# CXQuadcopter.net
KiCad netlist of a schematic drawn in Altium Designer
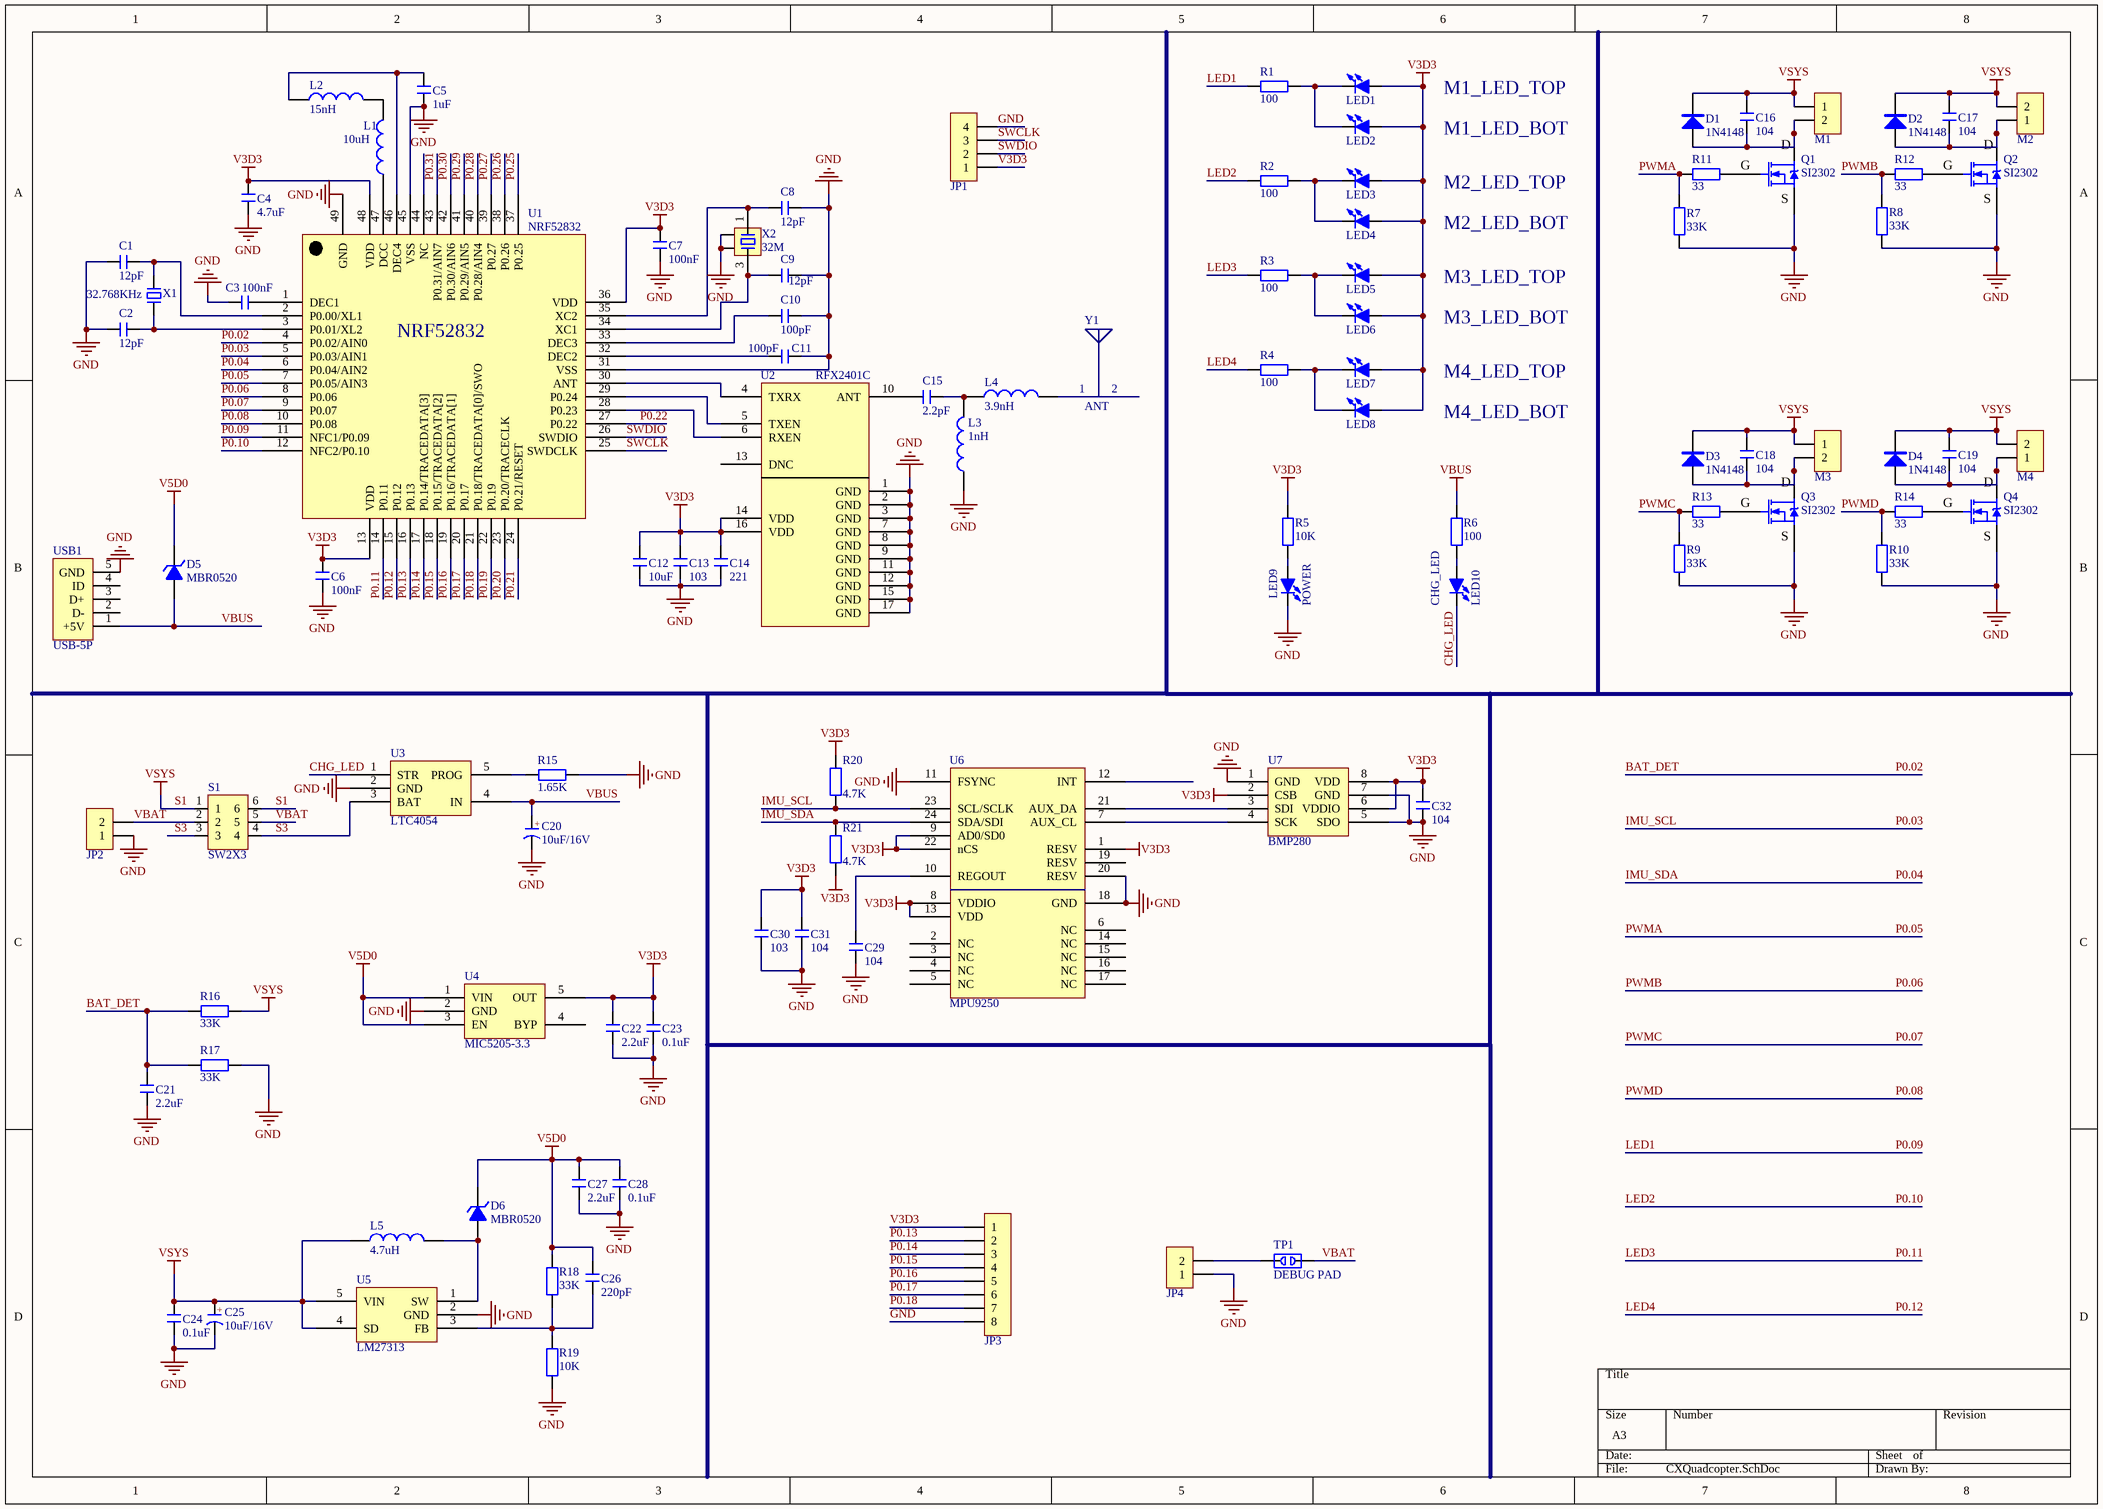
[diagram p0: CXQuadcopter.SchDoc]

(export (version "E")
  (design (tool "Eeschema 10.0.6"))
  (components
    (comp (ref "C1")
      (value "12pF")
      (footprint "C 0402")
      (description "无极性贴片电容")
      (fields (field (name "版权归属") "黎明电子style"))
      (libsource (lib "电阻-电容-电感") (part "C"))
    )
    (comp (ref "C2")
      (value "12pF")
      (footprint "C 0402")
      (description "无极性贴片电容")
      (fields (field (name "版权归属") "黎明电子style"))
      (libsource (lib "电阻-电容-电感") (part "C"))
    )
    (comp (ref "C3")
      (value "100nF")
      (footprint "C 0402")
      (description "无极性贴片电容")
      (fields (field (name "版权归属") "黎明电子style"))
      (libsource (lib "电阻-电容-电感") (part "C"))
    )
    (comp (ref "C4")
      (value "4.7uF")
      (footprint "C 0402")
      (description "无极性贴片电容")
      (fields (field (name "版权归属") "黎明电子style"))
      (libsource (lib "电阻-电容-电感") (part "C"))
    )
    (comp (ref "C5")
      (value "1uF")
      (footprint "C 0402")
      (description "无极性贴片电容")
      (fields (field (name "版权归属") "黎明电子style"))
      (libsource (lib "电阻-电容-电感") (part "C"))
    )
    (comp (ref "C6")
      (value "100nF")
      (footprint "C 0402")
      (description "无极性贴片电容")
      (fields (field (name "版权归属") "黎明电子style"))
      (libsource (lib "电阻-电容-电感") (part "C"))
    )
    (comp (ref "C7")
      (value "100nF")
      (footprint "C 0402")
      (description "无极性贴片电容")
      (fields (field (name "版权归属") "黎明电子style"))
      (libsource (lib "电阻-电容-电感") (part "C"))
    )
    (comp (ref "C8")
      (value "12pF")
      (footprint "C 0402")
      (description "无极性贴片电容")
      (fields (field (name "版权归属") "黎明电子style"))
      (libsource (lib "电阻-电容-电感") (part "C"))
    )
    (comp (ref "C9")
      (value "12pF")
      (footprint "C 0402")
      (description "无极性贴片电容")
      (fields (field (name "版权归属") "黎明电子style"))
      (libsource (lib "电阻-电容-电感") (part "C"))
    )
    (comp (ref "C10")
      (value "100pF")
      (footprint "C 0402")
      (description "无极性贴片电容")
      (fields (field (name "版权归属") "黎明电子style"))
      (libsource (lib "电阻-电容-电感") (part "C"))
    )
    (comp (ref "C11")
      (value "100pF")
      (footprint "C 0402")
      (description "无极性贴片电容")
      (fields (field (name "版权归属") "黎明电子style"))
      (libsource (lib "电阻-电容-电感") (part "C"))
    )
    (comp (ref "C12")
      (value "10uF")
      (footprint "C 0402")
      (description "无极性贴片电容")
      (fields (field (name "版权归属") "黎明电子style"))
      (libsource (lib "电阻-电容-电感") (part "C"))
    )
    (comp (ref "C13")
      (value "103")
      (footprint "C 0402")
      (description "无极性贴片电容")
      (fields (field (name "版权归属") "黎明电子style"))
      (libsource (lib "电阻-电容-电感") (part "C"))
    )
    (comp (ref "C14")
      (value "221")
      (footprint "C 0402")
      (description "无极性贴片电容")
      (fields (field (name "版权归属") "黎明电子style"))
      (libsource (lib "电阻-电容-电感") (part "C"))
    )
    (comp (ref "C15")
      (value "2.2pF")
      (footprint "C 0402")
      (description "无极性贴片电容")
      (fields (field (name "版权归属") "黎明电子style"))
      (libsource (lib "电阻-电容-电感") (part "C"))
    )
    (comp (ref "C16")
      (value "104")
      (footprint "C 0402")
      (description "无极性贴片电容")
      (fields (field (name "版权归属") "黎明电子style"))
      (libsource (lib "电阻-电容-电感") (part "C"))
    )
    (comp (ref "C17")
      (value "104")
      (footprint "C 0402")
      (description "无极性贴片电容")
      (fields (field (name "版权归属") "黎明电子style"))
      (libsource (lib "电阻-电容-电感") (part "C"))
    )
    (comp (ref "C18")
      (value "104")
      (footprint "C 0402")
      (description "无极性贴片电容")
      (fields (field (name "版权归属") "黎明电子style"))
      (libsource (lib "电阻-电容-电感") (part "C"))
    )
    (comp (ref "C19")
      (value "104")
      (footprint "C 0402")
      (description "无极性贴片电容")
      (fields (field (name "版权归属") "黎明电子style"))
      (libsource (lib "电阻-电容-电感") (part "C"))
    )
    (comp (ref "C20")
      (value "10uF/16V")
      (footprint "CD A(3216)")
      (description "贴片钽电容")
      (fields (field (name "版权归属") "黎明电子style"))
      (libsource (lib "电阻-电容-电感") (part "C-CD"))
    )
    (comp (ref "C21")
      (value "2.2uF")
      (footprint "C 0603")
      (description "无极性贴片电容")
      (fields (field (name "版权归属") "黎明电子style"))
      (libsource (lib "电阻-电容-电感") (part "C"))
    )
    (comp (ref "C22")
      (value "2.2uF")
      (footprint "C 0603")
      (description "无极性贴片电容")
      (fields (field (name "版权归属") "黎明电子style"))
      (libsource (lib "电阻-电容-电感") (part "C"))
    )
    (comp (ref "C23")
      (value "0.1uF")
      (footprint "C 0603")
      (description "无极性贴片电容")
      (fields (field (name "版权归属") "黎明电子style"))
      (libsource (lib "电阻-电容-电感") (part "C"))
    )
    (comp (ref "C24")
      (value "0.1uF")
      (footprint "C 0603")
      (description "无极性贴片电容")
      (fields (field (name "版权归属") "黎明电子style"))
      (libsource (lib "电阻-电容-电感") (part "C"))
    )
    (comp (ref "C25")
      (value "10uF/16V")
      (footprint "CD A(3216)")
      (description "贴片钽电容")
      (fields (field (name "版权归属") "黎明电子style"))
      (libsource (lib "电阻-电容-电感") (part "C-CD"))
    )
    (comp (ref "C26")
      (value "220pF")
      (footprint "C 0603")
      (description "无极性贴片电容")
      (fields (field (name "版权归属") "黎明电子style"))
      (libsource (lib "电阻-电容-电感") (part "C"))
    )
    (comp (ref "C27")
      (value "2.2uF")
      (footprint "C 0603")
      (description "无极性贴片电容")
      (fields (field (name "版权归属") "黎明电子style"))
      (libsource (lib "电阻-电容-电感") (part "C"))
    )
    (comp (ref "C28")
      (value "0.1uF")
      (footprint "C 0603")
      (description "无极性贴片电容")
      (fields (field (name "版权归属") "黎明电子style"))
      (libsource (lib "电阻-电容-电感") (part "C"))
    )
    (comp (ref "C29")
      (value "104")
      (footprint "C 0603")
      (description "无极性贴片电容")
      (fields (field (name "版权归属") "黎明电子style"))
      (libsource (lib "电阻-电容-电感") (part "C"))
    )
    (comp (ref "C30")
      (value "103")
      (footprint "C 0603")
      (description "无极性贴片电容")
      (fields (field (name "版权归属") "黎明电子style"))
      (libsource (lib "电阻-电容-电感") (part "C"))
    )
    (comp (ref "C31")
      (value "104")
      (footprint "C 0603")
      (description "无极性贴片电容")
      (fields (field (name "版权归属") "黎明电子style"))
      (libsource (lib "电阻-电容-电感") (part "C"))
    )
    (comp (ref "C32")
      (value "104")
      (footprint "C 0603")
      (description "无极性贴片电容")
      (fields (field (name "版权归属") "黎明电子style"))
      (libsource (lib "电阻-电容-电感") (part "C"))
    )
    (comp (ref "D1")
      (value "1N4148")
      (footprint "MINI_MELF (LL34)")
      (description "高速开关二极管")
      (fields (field (name "版权归属") "黎明电子style"))
      (libsource (lib "二极管-整流桥") (part "1N4148"))
    )
    (comp (ref "D2")
      (value "1N4148")
      (footprint "MINI_MELF (LL34)")
      (description "高速开关二极管")
      (fields (field (name "版权归属") "黎明电子style"))
      (libsource (lib "二极管-整流桥") (part "1N4148"))
    )
    (comp (ref "D3")
      (value "1N4148")
      (footprint "MINI_MELF (LL34)")
      (description "高速开关二极管")
      (fields (field (name "版权归属") "黎明电子style"))
      (libsource (lib "二极管-整流桥") (part "1N4148"))
    )
    (comp (ref "D4")
      (value "1N4148")
      (footprint "MINI_MELF (LL34)")
      (description "高速开关二极管")
      (fields (field (name "版权归属") "黎明电子style"))
      (libsource (lib "二极管-整流桥") (part "1N4148"))
    )
    (comp (ref "D5")
      (value "MBR0520")
      (footprint "DO-35")
      (description "12V/0.5W稳压管")
      (fields (field (name "版权归属") "黎明电子style"))
      (libsource (lib "二极管-整流桥") (part "1N4106"))
    )
    (comp (ref "D6")
      (value "MBR0520")
      (footprint "DO-35")
      (description "12V/0.5W稳压管")
      (fields (field (name "版权归属") "黎明电子style"))
      (libsource (lib "二极管-整流桥") (part "1N4106"))
    )
    (comp (ref "JP1")
      (value "HDR-1X4")
      (footprint "HDR2.54 S-W-4P")
      (description "4P接插件")
      (fields (field (name "版权归属") "黎明电子style"))
      (libsource (lib "接插件") (part "Header 4"))
    )
    (comp (ref "JP2")
      (value "HDR-1X2")
      (footprint "HDR-1X2")
      (description "2P接插件")
      (fields (field (name "版权归属") "黎明电子style"))
      (libsource (lib "") (part "Header 2_2"))
    )
    (comp (ref "JP3")
      (value "HDR-1X8")
      (footprint "HDR2.54 S-W-8P_M")
      (description "8P接插件")
      (fields (field (name "版权归属") "黎明电子style"))
      (libsource (lib "接插件") (part "Header 8"))
    )
    (comp (ref "JP4")
      (value "HDR-1X2")
      (footprint "HDR-1X2")
      (description "2P接插件")
      (fields (field (name "版权归属") "黎明电子style"))
      (libsource (lib "") (part "Header 2_2"))
    )
    (comp (ref "L1")
      (value "10uH")
      (footprint "L 0402")
      (description "小功率贴片电感")
      (fields (field (name "版权归属") "黎明电子style"))
      (libsource (lib "电阻-电容-电感") (part "L"))
    )
    (comp (ref "L2")
      (value "15nH")
      (footprint "L 0402")
      (description "小功率贴片电感")
      (fields (field (name "版权归属") "黎明电子style"))
      (libsource (lib "电阻-电容-电感") (part "L"))
    )
    (comp (ref "L3")
      (value "1nH")
      (footprint "L 0402")
      (description "小功率贴片电感")
      (fields (field (name "版权归属") "黎明电子style"))
      (libsource (lib "电阻-电容-电感") (part "L"))
    )
    (comp (ref "L4")
      (value "3.9nH")
      (footprint "L 0402")
      (description "小功率贴片电感")
      (fields (field (name "版权归属") "黎明电子style"))
      (libsource (lib "电阻-电容-电感") (part "L"))
    )
    (comp (ref "L5")
      (value "4.7uH")
      (footprint "L 0402")
      (description "小功率贴片电感")
      (fields (field (name "版权归属") "黎明电子style"))
      (libsource (lib "电阻-电容-电感") (part "L"))
    )
    (comp (ref "LED1")
      (value "红色")
      (footprint "LED 0603R")
      (description "贴片LED")
      (fields (field (name "版权归属") "黎明电子style"))
      (libsource (lib "LED") (part "LED-SMD"))
    )
    (comp (ref "LED2")
      (value "红色")
      (footprint "LED 0603R")
      (description "贴片LED")
      (fields (field (name "版权归属") "黎明电子style"))
      (libsource (lib "LED") (part "LED-SMD"))
    )
    (comp (ref "LED3")
      (value "红色")
      (footprint "LED 0603R")
      (description "贴片LED")
      (fields (field (name "版权归属") "黎明电子style"))
      (libsource (lib "LED") (part "LED-SMD"))
    )
    (comp (ref "LED4")
      (value "红色")
      (footprint "LED 0603R")
      (description "贴片LED")
      (fields (field (name "版权归属") "黎明电子style"))
      (libsource (lib "LED") (part "LED-SMD"))
    )
    (comp (ref "LED5")
      (value "红色")
      (footprint "LED 0603R")
      (description "贴片LED")
      (fields (field (name "版权归属") "黎明电子style"))
      (libsource (lib "LED") (part "LED-SMD"))
    )
    (comp (ref "LED6")
      (value "红色")
      (footprint "LED 0603R")
      (description "贴片LED")
      (fields (field (name "版权归属") "黎明电子style"))
      (libsource (lib "LED") (part "LED-SMD"))
    )
    (comp (ref "LED7")
      (value "红色")
      (footprint "LED 0603R")
      (description "贴片LED")
      (fields (field (name "版权归属") "黎明电子style"))
      (libsource (lib "LED") (part "LED-SMD"))
    )
    (comp (ref "LED8")
      (value "红色")
      (footprint "LED 0603R")
      (description "贴片LED")
      (fields (field (name "版权归属") "黎明电子style"))
      (libsource (lib "LED") (part "LED-SMD"))
    )
    (comp (ref "LED9")
      (value "POWER")
      (footprint "LED 0603R")
      (description "贴片LED")
      (fields (field (name "版权归属") "黎明电子style"))
      (libsource (lib "LED") (part "LED-SMD"))
    )
    (comp (ref "LED10")
      (value "CHG_LED")
      (footprint "LED 0603R")
      (description "贴片LED")
      (fields (field (name "版权归属") "黎明电子style"))
      (libsource (lib "LED") (part "LED-SMD"))
    )
    (comp (ref "M1")
      (value "HDR-1X2")
      (footprint "HDR-1X2")
      (description "2P接插件")
      (fields (field (name "版权归属") "黎明电子style"))
      (libsource (lib "接插件") (part "Header 2"))
    )
    (comp (ref "M2")
      (value "HDR-1X2")
      (footprint "HDR-1X2")
      (description "2P接插件")
      (fields (field (name "版权归属") "黎明电子style"))
      (libsource (lib "") (part "Header 2_1"))
    )
    (comp (ref "M3")
      (value "HDR-1X2")
      (footprint "HDR-1X2")
      (description "2P接插件")
      (fields (field (name "版权归属") "黎明电子style"))
      (libsource (lib "接插件") (part "Header 2"))
    )
    (comp (ref "M4")
      (value "HDR-1X2")
      (footprint "HDR-1X2")
      (description "2P接插件")
      (fields (field (name "版权归属") "黎明电子style"))
      (libsource (lib "") (part "Header 2_1"))
    )
    (comp (ref "Q1")
      (value "SI2302")
      (footprint "SOT23-3N")
      (description "N沟道场效应管")
      (fields (field (name "版权归属") "黎明电子style"))
      (libsource (lib "场效应管-可控硅") (part "SI2302"))
    )
    (comp (ref "Q2")
      (value "SI2302")
      (footprint "SOT23-3N")
      (description "N沟道场效应管")
      (fields (field (name "版权归属") "黎明电子style"))
      (libsource (lib "场效应管-可控硅") (part "SI2302"))
    )
    (comp (ref "Q3")
      (value "SI2302")
      (footprint "SOT23-3N")
      (description "N沟道场效应管")
      (fields (field (name "版权归属") "黎明电子style"))
      (libsource (lib "场效应管-可控硅") (part "SI2302"))
    )
    (comp (ref "Q4")
      (value "SI2302")
      (footprint "SOT23-3N")
      (description "N沟道场效应管")
      (fields (field (name "版权归属") "黎明电子style"))
      (libsource (lib "场效应管-可控硅") (part "SI2302"))
    )
    (comp (ref "R1")
      (value "100")
      (footprint "R 0603")
      (description "贴片电阻")
      (fields (field (name "版权归属") "黎明电子style"))
      (libsource (lib "电阻-电容-电感") (part "R"))
    )
    (comp (ref "R2")
      (value "100")
      (footprint "R 0603")
      (description "贴片电阻")
      (fields (field (name "版权归属") "黎明电子style"))
      (libsource (lib "电阻-电容-电感") (part "R"))
    )
    (comp (ref "R3")
      (value "100")
      (footprint "R 0603")
      (description "贴片电阻")
      (fields (field (name "版权归属") "黎明电子style"))
      (libsource (lib "电阻-电容-电感") (part "R"))
    )
    (comp (ref "R4")
      (value "100")
      (footprint "R 0603")
      (description "贴片电阻")
      (fields (field (name "版权归属") "黎明电子style"))
      (libsource (lib "电阻-电容-电感") (part "R"))
    )
    (comp (ref "R5")
      (value "10K")
      (footprint "R 0603")
      (description "贴片电阻")
      (fields (field (name "版权归属") "黎明电子style"))
      (libsource (lib "电阻-电容-电感") (part "R"))
    )
    (comp (ref "R6")
      (value "100")
      (footprint "R 0603")
      (description "贴片电阻")
      (fields (field (name "版权归属") "黎明电子style"))
      (libsource (lib "电阻-电容-电感") (part "R"))
    )
    (comp (ref "R7")
      (value "33K")
      (footprint "R 0603")
      (description "贴片电阻")
      (fields (field (name "版权归属") "黎明电子style"))
      (libsource (lib "电阻-电容-电感") (part "R"))
    )
    (comp (ref "R8")
      (value "33K")
      (footprint "R 0603")
      (description "贴片电阻")
      (fields (field (name "版权归属") "黎明电子style"))
      (libsource (lib "电阻-电容-电感") (part "R"))
    )
    (comp (ref "R9")
      (value "33K")
      (footprint "R 0603")
      (description "贴片电阻")
      (fields (field (name "版权归属") "黎明电子style"))
      (libsource (lib "电阻-电容-电感") (part "R"))
    )
    (comp (ref "R10")
      (value "33K")
      (footprint "R 0603")
      (description "贴片电阻")
      (fields (field (name "版权归属") "黎明电子style"))
      (libsource (lib "电阻-电容-电感") (part "R"))
    )
    (comp (ref "R11")
      (value "33")
      (footprint "R 0603")
      (description "贴片电阻")
      (fields (field (name "版权归属") "黎明电子style"))
      (libsource (lib "电阻-电容-电感") (part "R"))
    )
    (comp (ref "R12")
      (value "33")
      (footprint "R 0603")
      (description "贴片电阻")
      (fields (field (name "版权归属") "黎明电子style"))
      (libsource (lib "电阻-电容-电感") (part "R"))
    )
    (comp (ref "R13")
      (value "33")
      (footprint "R 0603")
      (description "贴片电阻")
      (fields (field (name "版权归属") "黎明电子style"))
      (libsource (lib "电阻-电容-电感") (part "R"))
    )
    (comp (ref "R14")
      (value "33")
      (footprint "R 0603")
      (description "贴片电阻")
      (fields (field (name "版权归属") "黎明电子style"))
      (libsource (lib "电阻-电容-电感") (part "R"))
    )
    (comp (ref "R15")
      (value "1.65K")
      (footprint "R 0603")
      (description "贴片电阻")
      (fields (field (name "版权归属") "黎明电子style"))
      (libsource (lib "电阻-电容-电感") (part "R"))
    )
    (comp (ref "R16")
      (value "33K")
      (footprint "R 0603")
      (description "贴片电阻")
      (fields (field (name "版权归属") "黎明电子style"))
      (libsource (lib "电阻-电容-电感") (part "R"))
    )
    (comp (ref "R17")
      (value "33K")
      (footprint "R 0603")
      (description "贴片电阻")
      (fields (field (name "版权归属") "黎明电子style"))
      (libsource (lib "电阻-电容-电感") (part "R"))
    )
    (comp (ref "R18")
      (value "33K")
      (footprint "R 0603")
      (description "贴片电阻")
      (fields (field (name "版权归属") "黎明电子style"))
      (libsource (lib "电阻-电容-电感") (part "R"))
    )
    (comp (ref "R19")
      (value "10K")
      (footprint "R 0603")
      (description "贴片电阻")
      (fields (field (name "版权归属") "黎明电子style"))
      (libsource (lib "电阻-电容-电感") (part "R"))
    )
    (comp (ref "R20")
      (value "4.7K")
      (footprint "R 0603")
      (description "贴片电阻")
      (fields (field (name "版权归属") "黎明电子style"))
      (libsource (lib "电阻-电容-电感") (part "R"))
    )
    (comp (ref "R21")
      (value "4.7K")
      (footprint "R 0603")
      (description "贴片电阻")
      (fields (field (name "版权归属") "黎明电子style"))
      (libsource (lib "电阻-电容-电感") (part "R"))
    )
    (comp (ref "S1") (value "SW2X3") (libsource (lib "ZhuhcADLib") (part "Switch")))
    (comp (ref "TP1")
      (value "DEBUG PAD")
      (footprint "DEBUG PAD2")
      (description "调试断点焊盘")
      (fields (field (name "版权归属") "黎明电子style"))
      (libsource (lib "未分类器件") (part "DEBUG"))
    )
    (comp (ref "U1") (value "NRF52832") (libsource (lib "ZhuhcADLib") (part "NRF52832")))
    (comp (ref "U2") (value "RFX2401C") (libsource (lib "ZhuhcADLib") (part "RFX2401C")))
    (comp (ref "U3") (value "LTC4054") (libsource (lib "ZhuhcADLib") (part "LTC4054")))
    (comp (ref "U4") (value "MIC5205-3.3") (libsource (lib "ZhuhcADLib") (part "MIC5205-3.3")))
    (comp (ref "U5") (value "LM27313") (libsource (lib "ZhuhcADLib") (part "LM27313")))
    (comp (ref "U6") (value "MPU9250") (libsource (lib "ZhuhcADLib") (part "MPU9250")))
    (comp (ref "U7") (value "BMP280") (libsource (lib "ZhuhcADLib") (part "BMP280")))
    (comp (ref "USB1")
      (value "USB-5P")
      (footprint "USB-MICRO_A")
      (description "微型USB母座")
      (fields (field (name "版权归属") "黎明电子style"))
      (libsource (lib "接口类") (part "USB-5P"))
    )
    (comp (ref "X1")
      (value "32.768KHz")
      (footprint "XTAL-3X8H")
      (description "2脚晶振")
      (fields (field (name "版权归属") "黎明电子style"))
      (libsource (lib "保险丝-晶振") (part "XTAL-2"))
    )
    (comp (ref "X2")
      (value "32M")
      (footprint "XTAL-5032")
      (description "4脚晶振")
      (fields (field (name "版权归属") "黎明电子style"))
      (libsource (lib "保险丝-晶振") (part "XTAL-4"))
    )
    (comp (ref "Y1") (value "ANT") (libsource (lib "ZhuhcADLib") (part "ANT")))
  )
  (nets
    (net (code "1") (name "/BAT_DET") (class "Default")
      (node (ref "C21") (pin "2") (pinfunction "2_2") (pintype "passive"))
      (node (ref "R16") (pin "1") (pinfunction "1_1") (pintype "passive"))
      (node (ref "R17") (pin "1") (pinfunction "1_1") (pintype "passive"))
      (node (ref "U1") (pin "4") (pinfunction "P0.02/AIN0_4") (pintype "passive"))
    )
    (net (code "2") (name "/CHG_LED") (class "Default")
      (node (ref "LED10") (pin "2") (pinfunction "K_2") (pintype "passive"))
      (node (ref "U3") (pin "1") (pinfunction "STR_1") (pintype "passive"))
    )
    (net (code "3") (name "/IMU_SCL") (class "Default")
      (node (ref "R20") (pin "1") (pinfunction "1_1") (pintype "passive"))
      (node (ref "U1") (pin "5") (pinfunction "P0.03/AIN1_5") (pintype "passive"))
      (node (ref "U6") (pin "23") (pinfunction "SCL/SCLK_23") (pintype "passive"))
    )
    (net (code "4") (name "/IMU_SDA") (class "Default")
      (node (ref "R21") (pin "2") (pinfunction "2_2") (pintype "passive"))
      (node (ref "U1") (pin "6") (pinfunction "P0.04/AIN2_6") (pintype "passive"))
      (node (ref "U6") (pin "24") (pinfunction "SDA/SDI_24") (pintype "passive"))
    )
    (net (code "5") (name "/LED1") (class "Default")
      (node (ref "R1") (pin "2") (pinfunction "2_2") (pintype "passive"))
      (node (ref "U1") (pin "11") (pinfunction "NFC1/P0.09_11") (pintype "passive"))
    )
    (net (code "6") (name "/LED2") (class "Default")
      (node (ref "R2") (pin "2") (pinfunction "2_2") (pintype "passive"))
      (node (ref "U1") (pin "12") (pinfunction "NFC2/P0.10_12") (pintype "passive"))
    )
    (net (code "7") (name "/LED3") (class "Default")
      (node (ref "R3") (pin "2") (pinfunction "2_2") (pintype "passive"))
      (node (ref "U1") (pin "14") (pinfunction "P0.11_14") (pintype "passive"))
    )
    (net (code "8") (name "/LED4") (class "Default")
      (node (ref "R4") (pin "2") (pinfunction "2_2") (pintype "passive"))
      (node (ref "U1") (pin "15") (pinfunction "P0.12_15") (pintype "passive"))
    )
    (net (code "9") (name "/P0.05") (class "Default")
      (node (ref "R11") (pin "2") (pinfunction "2_2") (pintype "passive"))
      (node (ref "R7") (pin "2") (pinfunction "2_2") (pintype "passive"))
      (node (ref "U1") (pin "7") (pinfunction "P0.05/AIN3_7") (pintype "passive"))
    )
    (net (code "10") (name "/P0.06") (class "Default")
      (node (ref "R12") (pin "2") (pinfunction "2_2") (pintype "passive"))
      (node (ref "R8") (pin "2") (pinfunction "2_2") (pintype "passive"))
      (node (ref "U1") (pin "8") (pinfunction "P0.06_8") (pintype "passive"))
    )
    (net (code "11") (name "/P0.07") (class "Default")
      (node (ref "R13") (pin "2") (pinfunction "2_2") (pintype "passive"))
      (node (ref "R9") (pin "2") (pinfunction "2_2") (pintype "passive"))
      (node (ref "U1") (pin "9") (pinfunction "P0.07_9") (pintype "passive"))
    )
    (net (code "12") (name "/P0.08") (class "Default")
      (node (ref "R10") (pin "2") (pinfunction "2_2") (pintype "passive"))
      (node (ref "R14") (pin "2") (pinfunction "2_2") (pintype "passive"))
      (node (ref "U1") (pin "10") (pinfunction "P0.08_10") (pintype "passive"))
    )
    (net (code "13") (name "/P0.13") (class "Default")
      (node (ref "JP3") (pin "2") (pinfunction "2_2") (pintype "passive"))
      (node (ref "U1") (pin "16") (pinfunction "P0.13_16") (pintype "passive"))
    )
    (net (code "14") (name "/P0.14") (class "Default")
      (node (ref "JP3") (pin "3") (pinfunction "3_3") (pintype "passive"))
      (node (ref "U1") (pin "17") (pinfunction "P0.14/TRACEDATA[3]_17") (pintype "passive"))
    )
    (net (code "15") (name "/P0.15") (class "Default")
      (node (ref "JP3") (pin "4") (pinfunction "4_4") (pintype "passive"))
      (node (ref "U1") (pin "18") (pinfunction "P0.15/TRACEDATA[2]_18") (pintype "passive"))
    )
    (net (code "16") (name "/P0.16") (class "Default")
      (node (ref "JP3") (pin "5") (pinfunction "5_5") (pintype "passive"))
      (node (ref "U1") (pin "19") (pinfunction "P0.16/TRACEDATA[1]_19") (pintype "passive"))
    )
    (net (code "17") (name "/P0.17") (class "Default")
      (node (ref "JP3") (pin "6") (pinfunction "6_6") (pintype "passive"))
      (node (ref "U1") (pin "20") (pinfunction "P0.17_20") (pintype "passive"))
    )
    (net (code "18") (name "/P0.18") (class "Default")
      (node (ref "JP3") (pin "7") (pinfunction "7_7") (pintype "passive"))
      (node (ref "U1") (pin "21") (pinfunction "P0.18/TRACEDATA[0]/SWO_21") (pintype "passive"))
    )
    (net (code "19") (name "/P0.19") (class "Default")
      (node (ref "U1") (pin "22") (pinfunction "P0.19_22") (pintype "passive"))
    )
    (net (code "20") (name "/P0.20") (class "Default")
      (node (ref "U1") (pin "23") (pinfunction "P0.20/TRACECLK_23") (pintype "passive"))
    )
    (net (code "21") (name "/P0.21") (class "Default")
      (node (ref "U1") (pin "24") (pinfunction "P0.21/RESET_24") (pintype "passive"))
    )
    (net (code "22") (name "/P0.22") (class "Default")
      (node (ref "U1") (pin "27") (pinfunction "P0.22_27") (pintype "passive"))
    )
    (net (code "23") (name "/P0.25") (class "Default")
      (node (ref "U1") (pin "37") (pinfunction "P0.25_37") (pintype "passive"))
    )
    (net (code "24") (name "/P0.26") (class "Default")
      (node (ref "U1") (pin "38") (pinfunction "P0.26_38") (pintype "passive"))
    )
    (net (code "25") (name "/P0.27") (class "Default")
      (node (ref "U1") (pin "39") (pinfunction "P0.27_39") (pintype "passive"))
    )
    (net (code "26") (name "/P0.28") (class "Default")
      (node (ref "U1") (pin "40") (pinfunction "P0.28/AIN4_40") (pintype "passive"))
    )
    (net (code "27") (name "/P0.29") (class "Default")
      (node (ref "U1") (pin "41") (pinfunction "P0.29/AIN5_41") (pintype "passive"))
    )
    (net (code "28") (name "/P0.30") (class "Default")
      (node (ref "U1") (pin "42") (pinfunction "P0.30/AIN6_42") (pintype "passive"))
    )
    (net (code "29") (name "/P0.31") (class "Default")
      (node (ref "U1") (pin "43") (pinfunction "P0.31/AIN7_43") (pintype "passive"))
    )
    (net (code "30") (name "/S3") (class "Default")
      (node (ref "S1") (pin "3") (pinfunction "3_3") (pintype "passive"))
      (node (ref "S1") (pin "4") (pinfunction "4_4") (pintype "passive"))
      (node (ref "U3") (pin "3") (pinfunction "BAT_3") (pintype "passive"))
    )
    (net (code "31") (name "/SWCLK") (class "Default")
      (node (ref "JP1") (pin "3") (pinfunction "3_3") (pintype "passive"))
      (node (ref "U1") (pin "25") (pinfunction "SWDCLK_25") (pintype "passive"))
    )
    (net (code "32") (name "/SWDIO") (class "Default")
      (node (ref "JP1") (pin "2") (pinfunction "2_2") (pintype "passive"))
      (node (ref "U1") (pin "26") (pinfunction "SWDIO_26") (pintype "passive"))
    )
    (net (code "33") (name "/VBAT") (class "Default")
      (node (ref "JP2") (pin "2") (pinfunction "2_2") (pintype "passive"))
      (node (ref "S1") (pin "2") (pinfunction "2_2") (pintype "passive"))
      (node (ref "S1") (pin "5") (pinfunction "5_5") (pintype "passive"))
      (node (ref "TP1") (pin "2") (pinfunction "2_2") (pintype "passive"))
    )
    (net (code "34") (name "GND") (class "Default")
      (node (ref "C1") (pin "1") (pinfunction "1_1") (pintype "passive"))
      (node (ref "C10") (pin "2") (pinfunction "2_2") (pintype "passive"))
      (node (ref "C11") (pin "2") (pinfunction "2_2") (pintype "passive"))
      (node (ref "C12") (pin "1") (pinfunction "1_1") (pintype "passive"))
      (node (ref "C13") (pin "1") (pinfunction "1_1") (pintype "passive"))
      (node (ref "C14") (pin "1") (pinfunction "1_1") (pintype "passive"))
      (node (ref "C2") (pin "1") (pinfunction "1_1") (pintype "passive"))
      (node (ref "C20") (pin "2") (pinfunction "K_2") (pintype "passive"))
      (node (ref "C21") (pin "1") (pinfunction "1_1") (pintype "passive"))
      (node (ref "C22") (pin "1") (pinfunction "1_1") (pintype "passive"))
      (node (ref "C23") (pin "1") (pinfunction "1_1") (pintype "passive"))
      (node (ref "C24") (pin "1") (pinfunction "1_1") (pintype "passive"))
      (node (ref "C25") (pin "2") (pinfunction "K_2") (pintype "passive"))
      (node (ref "C27") (pin "1") (pinfunction "1_1") (pintype "passive"))
      (node (ref "C28") (pin "1") (pinfunction "1_1") (pintype "passive"))
      (node (ref "C29") (pin "1") (pinfunction "1_1") (pintype "passive"))
      (node (ref "C3") (pin "1") (pinfunction "1_1") (pintype "passive"))
      (node (ref "C30") (pin "1") (pinfunction "1_1") (pintype "passive"))
      (node (ref "C31") (pin "1") (pinfunction "1_1") (pintype "passive"))
      (node (ref "C32") (pin "1") (pinfunction "1_1") (pintype "passive"))
      (node (ref "C4") (pin "1") (pinfunction "1_1") (pintype "passive"))
      (node (ref "C5") (pin "1") (pinfunction "1_1") (pintype "passive"))
      (node (ref "C6") (pin "1") (pinfunction "1_1") (pintype "passive"))
      (node (ref "C7") (pin "1") (pinfunction "1_1") (pintype "passive"))
      (node (ref "C8") (pin "2") (pinfunction "2_2") (pintype "passive"))
      (node (ref "C9") (pin "2") (pinfunction "2_2") (pintype "passive"))
      (node (ref "JP1") (pin "4") (pinfunction "4_4") (pintype "passive"))
      (node (ref "JP2") (pin "1") (pinfunction "1_1") (pintype "passive"))
      (node (ref "JP3") (pin "8") (pinfunction "8_8") (pintype "passive"))
      (node (ref "JP4") (pin "1") (pinfunction "1_1") (pintype "passive"))
      (node (ref "L3") (pin "1") (pinfunction "1_1") (pintype "passive"))
      (node (ref "LED9") (pin "2") (pinfunction "K_2") (pintype "passive"))
      (node (ref "Q1") (pin "2") (pinfunction "S_2") (pintype "passive"))
      (node (ref "Q2") (pin "2") (pinfunction "S_2") (pintype "passive"))
      (node (ref "Q3") (pin "2") (pinfunction "S_2") (pintype "passive"))
      (node (ref "Q4") (pin "2") (pinfunction "S_2") (pintype "passive"))
      (node (ref "R10") (pin "1") (pinfunction "1_1") (pintype "passive"))
      (node (ref "R15") (pin "2") (pinfunction "2_2") (pintype "passive"))
      (node (ref "R17") (pin "2") (pinfunction "2_2") (pintype "passive"))
      (node (ref "R19") (pin "1") (pinfunction "1_1") (pintype "passive"))
      (node (ref "R7") (pin "1") (pinfunction "1_1") (pintype "passive"))
      (node (ref "R8") (pin "1") (pinfunction "1_1") (pintype "passive"))
      (node (ref "R9") (pin "1") (pinfunction "1_1") (pintype "passive"))
      (node (ref "U1") (pin "31") (pinfunction "VSS_31") (pintype "passive"))
      (node (ref "U1") (pin "45") (pinfunction "VSS_45") (pintype "passive"))
      (node (ref "U1") (pin "49") (pinfunction "GND_49") (pintype "passive"))
      (node (ref "U2") (pin "1") (pinfunction "GND_1") (pintype "passive"))
      (node (ref "U2") (pin "11") (pinfunction "GND_11") (pintype "passive"))
      (node (ref "U2") (pin "12") (pinfunction "GND_12") (pintype "passive"))
      (node (ref "U2") (pin "15") (pinfunction "GND_15") (pintype "passive"))
      (node (ref "U2") (pin "17") (pinfunction "GND_17") (pintype "passive"))
      (node (ref "U2") (pin "2") (pinfunction "GND_2") (pintype "passive"))
      (node (ref "U2") (pin "3") (pinfunction "GND_3") (pintype "passive"))
      (node (ref "U2") (pin "7") (pinfunction "GND_7") (pintype "passive"))
      (node (ref "U2") (pin "8") (pinfunction "GND_8") (pintype "passive"))
      (node (ref "U2") (pin "9") (pinfunction "GND_9") (pintype "passive"))
      (node (ref "U3") (pin "2") (pinfunction "GND_2") (pintype "passive"))
      (node (ref "U4") (pin "2") (pinfunction "GND_2") (pintype "passive"))
      (node (ref "U5") (pin "2") (pinfunction "GND_2") (pintype "passive"))
      (node (ref "U6") (pin "11") (pinfunction "FSYNC_11") (pintype "passive"))
      (node (ref "U6") (pin "18") (pinfunction "GND_18") (pintype "passive"))
      (node (ref "U6") (pin "20") (pinfunction "RESV_20") (pintype "passive"))
      (node (ref "U7") (pin "1") (pinfunction "GND_1") (pintype "passive"))
      (node (ref "U7") (pin "5") (pinfunction "SDO_5") (pintype "passive"))
      (node (ref "U7") (pin "7") (pinfunction "GND_7") (pintype "passive"))
      (node (ref "USB1") (pin "5") (pinfunction "GND_5") (pintype "passive"))
      (node (ref "X2") (pin "2") (pinfunction "2_2") (pintype "passive"))
      (node (ref "X2") (pin "4") (pinfunction "4_4") (pintype "passive"))
    )
    (net (code "35") (name "Net-(C15-Pad1)") (class "Default")
      (node (ref "C15") (pin "1") (pinfunction "1_1") (pintype "passive"))
      (node (ref "L3") (pin "2") (pinfunction "2_2") (pintype "passive"))
      (node (ref "L4") (pin "1") (pinfunction "1_1") (pintype "passive"))
    )
    (net (code "36") (name "Net-(D1-A)") (class "Default")
      (node (ref "C16") (pin "2") (pinfunction "2_2") (pintype "passive"))
      (node (ref "D1") (pin "1") (pinfunction "A_1") (pintype "passive"))
      (node (ref "M1") (pin "2") (pinfunction "2_2") (pintype "passive"))
      (node (ref "Q1") (pin "3") (pinfunction "D_3") (pintype "passive"))
    )
    (net (code "37") (name "Net-(D2-A)") (class "Default")
      (node (ref "C17") (pin "2") (pinfunction "2_2") (pintype "passive"))
      (node (ref "D2") (pin "1") (pinfunction "A_1") (pintype "passive"))
      (node (ref "M2") (pin "1") (pinfunction "1_1") (pintype "passive"))
      (node (ref "Q2") (pin "3") (pinfunction "D_3") (pintype "passive"))
    )
    (net (code "38") (name "Net-(D3-A)") (class "Default")
      (node (ref "C18") (pin "2") (pinfunction "2_2") (pintype "passive"))
      (node (ref "D3") (pin "1") (pinfunction "A_1") (pintype "passive"))
      (node (ref "M3") (pin "2") (pinfunction "2_2") (pintype "passive"))
      (node (ref "Q3") (pin "3") (pinfunction "D_3") (pintype "passive"))
    )
    (net (code "39") (name "Net-(D4-A)") (class "Default")
      (node (ref "C19") (pin "2") (pinfunction "2_2") (pintype "passive"))
      (node (ref "D4") (pin "1") (pinfunction "A_1") (pintype "passive"))
      (node (ref "M4") (pin "1") (pinfunction "1_1") (pintype "passive"))
      (node (ref "Q4") (pin "3") (pinfunction "D_3") (pintype "passive"))
    )
    (net (code "40") (name "Net-(D6-A)") (class "Default")
      (node (ref "D6") (pin "1") (pinfunction "A_1") (pintype "passive"))
      (node (ref "L5") (pin "2") (pinfunction "2_2") (pintype "passive"))
      (node (ref "U5") (pin "1") (pinfunction "SW_1") (pintype "passive"))
    )
    (net (code "41") (name "Net-(JP4-Pad2)") (class "Default")
      (node (ref "JP4") (pin "2") (pinfunction "2_2") (pintype "passive"))
      (node (ref "TP1") (pin "1") (pinfunction "1_1") (pintype "passive"))
    )
    (net (code "42") (name "Net-(L1-Pad2)") (class "Default")
      (node (ref "L1") (pin "2") (pinfunction "2_2") (pintype "passive"))
      (node (ref "L2") (pin "2") (pinfunction "2_2") (pintype "passive"))
    )
    (net (code "43") (name "Net-(L4-Pad2)") (class "Default")
      (node (ref "L4") (pin "2") (pinfunction "2_2") (pintype "passive"))
      (node (ref "Y1") (pin "1") (pinfunction "1_1") (pintype "passive"))
    )
    (net (code "44") (name "Net-(LED1-K)") (class "Default")
      (node (ref "LED1") (pin "2") (pinfunction "K_2") (pintype "passive"))
      (node (ref "LED2") (pin "2") (pinfunction "K_2") (pintype "passive"))
      (node (ref "R1") (pin "1") (pinfunction "1_1") (pintype "passive"))
    )
    (net (code "45") (name "Net-(LED3-K)") (class "Default")
      (node (ref "LED3") (pin "2") (pinfunction "K_2") (pintype "passive"))
      (node (ref "LED4") (pin "2") (pinfunction "K_2") (pintype "passive"))
      (node (ref "R2") (pin "1") (pinfunction "1_1") (pintype "passive"))
    )
    (net (code "46") (name "Net-(LED5-K)") (class "Default")
      (node (ref "LED5") (pin "2") (pinfunction "K_2") (pintype "passive"))
      (node (ref "LED6") (pin "2") (pinfunction "K_2") (pintype "passive"))
      (node (ref "R3") (pin "1") (pinfunction "1_1") (pintype "passive"))
    )
    (net (code "47") (name "Net-(LED7-K)") (class "Default")
      (node (ref "LED7") (pin "2") (pinfunction "K_2") (pintype "passive"))
      (node (ref "LED8") (pin "2") (pinfunction "K_2") (pintype "passive"))
      (node (ref "R4") (pin "1") (pinfunction "1_1") (pintype "passive"))
    )
    (net (code "48") (name "Net-(LED9-A)") (class "Default")
      (node (ref "LED9") (pin "1") (pinfunction "A_1") (pintype "passive"))
      (node (ref "R5") (pin "2") (pinfunction "2_2") (pintype "passive"))
    )
    (net (code "49") (name "Net-(LED10-A)") (class "Default")
      (node (ref "LED10") (pin "1") (pinfunction "A_1") (pintype "passive"))
      (node (ref "R6") (pin "2") (pinfunction "2_2") (pintype "passive"))
    )
    (net (code "50") (name "Net-(Q1-G)") (class "Default")
      (node (ref "Q1") (pin "1") (pinfunction "G_1") (pintype "passive"))
      (node (ref "R11") (pin "1") (pinfunction "1_1") (pintype "passive"))
    )
    (net (code "51") (name "Net-(Q2-G)") (class "Default")
      (node (ref "Q2") (pin "1") (pinfunction "G_1") (pintype "passive"))
      (node (ref "R12") (pin "1") (pinfunction "1_1") (pintype "passive"))
    )
    (net (code "52") (name "Net-(Q3-G)") (class "Default")
      (node (ref "Q3") (pin "1") (pinfunction "G_1") (pintype "passive"))
      (node (ref "R13") (pin "1") (pinfunction "1_1") (pintype "passive"))
    )
    (net (code "53") (name "Net-(Q4-G)") (class "Default")
      (node (ref "Q4") (pin "1") (pinfunction "G_1") (pintype "passive"))
      (node (ref "R14") (pin "1") (pinfunction "1_1") (pintype "passive"))
    )
    (net (code "54") (name "Net-(U1-ANT)") (class "Default")
      (node (ref "U1") (pin "30") (pinfunction "ANT_30") (pintype "passive"))
      (node (ref "U2") (pin "4") (pinfunction "TXRX_4") (pintype "passive"))
    )
    (net (code "55") (name "Net-(U1-DCC)") (class "Default")
      (node (ref "L1") (pin "1") (pinfunction "1_1") (pintype "passive"))
      (node (ref "U1") (pin "47") (pinfunction "DCC_47") (pintype "passive"))
    )
    (net (code "56") (name "Net-(U1-DEC1)") (class "Default")
      (node (ref "C3") (pin "2") (pinfunction "2_2") (pintype "passive"))
      (node (ref "U1") (pin "1") (pinfunction "DEC1_1") (pintype "passive"))
    )
    (net (code "57") (name "Net-(U1-DEC2)") (class "Default")
      (node (ref "C11") (pin "1") (pinfunction "1_1") (pintype "passive"))
      (node (ref "U1") (pin "32") (pinfunction "DEC2_32") (pintype "passive"))
    )
    (net (code "58") (name "Net-(U1-DEC3)") (class "Default")
      (node (ref "C10") (pin "1") (pinfunction "1_1") (pintype "passive"))
      (node (ref "U1") (pin "33") (pinfunction "DEC3_33") (pintype "passive"))
    )
    (net (code "59") (name "Net-(U1-DEC4)") (class "Default")
      (node (ref "C5") (pin "2") (pinfunction "2_2") (pintype "passive"))
      (node (ref "L2") (pin "1") (pinfunction "1_1") (pintype "passive"))
      (node (ref "U1") (pin "46") (pinfunction "DEC4_46") (pintype "passive"))
    )
    (net (code "60") (name "Net-(U1-P0.00{slash}XL1)") (class "Default")
      (node (ref "C1") (pin "2") (pinfunction "2_2") (pintype "passive"))
      (node (ref "U1") (pin "2") (pinfunction "P0.00/XL1_2") (pintype "passive"))
      (node (ref "X1") (pin "2") (pinfunction "2_2") (pintype "passive"))
    )
    (net (code "61") (name "Net-(U1-P0.01{slash}XL2)") (class "Default")
      (node (ref "C2") (pin "2") (pinfunction "2_2") (pintype "passive"))
      (node (ref "U1") (pin "3") (pinfunction "P0.01/XL2_3") (pintype "passive"))
      (node (ref "X1") (pin "1") (pinfunction "1_1") (pintype "passive"))
    )
    (net (code "62") (name "Net-(U1-P0.23)") (class "Default")
      (node (ref "U1") (pin "28") (pinfunction "P0.23_28") (pintype "passive"))
      (node (ref "U2") (pin "6") (pinfunction "RXEN_6") (pintype "passive"))
    )
    (net (code "63") (name "Net-(U1-P0.24)") (class "Default")
      (node (ref "U1") (pin "29") (pinfunction "P0.24_29") (pintype "passive"))
      (node (ref "U2") (pin "5") (pinfunction "TXEN_5") (pintype "passive"))
    )
    (net (code "64") (name "Net-(U1-XC1)") (class "Default")
      (node (ref "C9") (pin "1") (pinfunction "1_1") (pintype "passive"))
      (node (ref "U1") (pin "34") (pinfunction "XC1_34") (pintype "passive"))
      (node (ref "X2") (pin "3") (pinfunction "3_3") (pintype "passive"))
    )
    (net (code "65") (name "Net-(U1-XC2)") (class "Default")
      (node (ref "C8") (pin "1") (pinfunction "1_1") (pintype "passive"))
      (node (ref "U1") (pin "35") (pinfunction "XC2_35") (pintype "passive"))
      (node (ref "X2") (pin "1") (pinfunction "1_1") (pintype "passive"))
    )
    (net (code "66") (name "Net-(U2-ANT)") (class "Default")
      (node (ref "C15") (pin "2") (pinfunction "2_2") (pintype "passive"))
      (node (ref "U2") (pin "10") (pinfunction "ANT_10") (pintype "passive"))
    )
    (net (code "67") (name "Net-(U3-PROG)") (class "Default")
      (node (ref "R15") (pin "1") (pinfunction "1_1") (pintype "passive"))
      (node (ref "U3") (pin "5") (pinfunction "PROG_5") (pintype "passive"))
    )
    (net (code "68") (name "Net-(U5-FB)") (class "Default")
      (node (ref "C26") (pin "1") (pinfunction "1_1") (pintype "passive"))
      (node (ref "R18") (pin "1") (pinfunction "1_1") (pintype "passive"))
      (node (ref "R19") (pin "2") (pinfunction "2_2") (pintype "passive"))
      (node (ref "U5") (pin "3") (pinfunction "FB_3") (pintype "passive"))
    )
    (net (code "69") (name "Net-(U6-AUX_CL)") (class "Default")
      (node (ref "U6") (pin "7") (pinfunction "AUX_CL_7") (pintype "passive"))
      (node (ref "U7") (pin "4") (pinfunction "SCK_4") (pintype "passive"))
    )
    (net (code "70") (name "Net-(U6-AUX_DA)") (class "Default")
      (node (ref "U6") (pin "21") (pinfunction "AUX_DA_21") (pintype "passive"))
      (node (ref "U7") (pin "3") (pinfunction "SDI_3") (pintype "passive"))
    )
    (net (code "71") (name "Net-(U6-REGOUT)") (class "Default")
      (node (ref "C29") (pin "2") (pinfunction "2_2") (pintype "passive"))
      (node (ref "U6") (pin "10") (pinfunction "REGOUT_10") (pintype "passive"))
    )
    (net (code "72") (name "V3D3") (class "Default")
      (node (ref "C12") (pin "2") (pinfunction "2_2") (pintype "passive"))
      (node (ref "C13") (pin "2") (pinfunction "2_2") (pintype "passive"))
      (node (ref "C14") (pin "2") (pinfunction "2_2") (pintype "passive"))
      (node (ref "C22") (pin "2") (pinfunction "2_2") (pintype "passive"))
      (node (ref "C23") (pin "2") (pinfunction "2_2") (pintype "passive"))
      (node (ref "C30") (pin "2") (pinfunction "2_2") (pintype "passive"))
      (node (ref "C31") (pin "2") (pinfunction "2_2") (pintype "passive"))
      (node (ref "C32") (pin "2") (pinfunction "2_2") (pintype "passive"))
      (node (ref "C4") (pin "2") (pinfunction "2_2") (pintype "passive"))
      (node (ref "C6") (pin "2") (pinfunction "2_2") (pintype "passive"))
      (node (ref "C7") (pin "2") (pinfunction "2_2") (pintype "passive"))
      (node (ref "JP1") (pin "1") (pinfunction "1_1") (pintype "passive"))
      (node (ref "JP3") (pin "1") (pinfunction "1_1") (pintype "passive"))
      (node (ref "LED1") (pin "1") (pinfunction "A_1") (pintype "passive"))
      (node (ref "LED2") (pin "1") (pinfunction "A_1") (pintype "passive"))
      (node (ref "LED3") (pin "1") (pinfunction "A_1") (pintype "passive"))
      (node (ref "LED4") (pin "1") (pinfunction "A_1") (pintype "passive"))
      (node (ref "LED5") (pin "1") (pinfunction "A_1") (pintype "passive"))
      (node (ref "LED6") (pin "1") (pinfunction "A_1") (pintype "passive"))
      (node (ref "LED7") (pin "1") (pinfunction "A_1") (pintype "passive"))
      (node (ref "LED8") (pin "1") (pinfunction "A_1") (pintype "passive"))
      (node (ref "R20") (pin "2") (pinfunction "2_2") (pintype "passive"))
      (node (ref "R21") (pin "1") (pinfunction "1_1") (pintype "passive"))
      (node (ref "R5") (pin "1") (pinfunction "1_1") (pintype "passive"))
      (node (ref "U1") (pin "13") (pinfunction "VDD_13") (pintype "passive"))
      (node (ref "U1") (pin "36") (pinfunction "VDD_36") (pintype "passive"))
      (node (ref "U1") (pin "48") (pinfunction "VDD_48") (pintype "passive"))
      (node (ref "U2") (pin "14") (pinfunction "VDD_14") (pintype "passive"))
      (node (ref "U2") (pin "16") (pinfunction "VDD_16") (pintype "passive"))
      (node (ref "U4") (pin "5") (pinfunction "OUT_5") (pintype "passive"))
      (node (ref "U6") (pin "1") (pinfunction "RESV_1") (pintype "passive"))
      (node (ref "U6") (pin "13") (pinfunction "VDD_13") (pintype "passive"))
      (node (ref "U6") (pin "22") (pinfunction "nCS_22") (pintype "passive"))
      (node (ref "U6") (pin "8") (pinfunction "VDDIO_8") (pintype "passive"))
      (node (ref "U6") (pin "9") (pinfunction "AD0/SD0_9") (pintype "passive"))
      (node (ref "U7") (pin "2") (pinfunction "CSB_2") (pintype "passive"))
      (node (ref "U7") (pin "6") (pinfunction "VDDIO_6") (pintype "passive"))
      (node (ref "U7") (pin "8") (pinfunction "VDD_8") (pintype "passive"))
    )
    (net (code "73") (name "V5D0") (class "Default")
      (node (ref "C26") (pin "2") (pinfunction "2_2") (pintype "passive"))
      (node (ref "C27") (pin "2") (pinfunction "2_2") (pintype "passive"))
      (node (ref "C28") (pin "2") (pinfunction "2_2") (pintype "passive"))
      (node (ref "D5") (pin "2") (pinfunction "K_2") (pintype "passive"))
      (node (ref "D6") (pin "2") (pinfunction "K_2") (pintype "passive"))
      (node (ref "R18") (pin "2") (pinfunction "2_2") (pintype "passive"))
      (node (ref "U4") (pin "1") (pinfunction "VIN_1") (pintype "passive"))
      (node (ref "U4") (pin "3") (pinfunction "EN_3") (pintype "passive"))
    )
    (net (code "74") (name "VBUS") (class "Default")
      (node (ref "C20") (pin "1") (pinfunction "A_1") (pintype "passive"))
      (node (ref "D5") (pin "1") (pinfunction "A_1") (pintype "passive"))
      (node (ref "R6") (pin "1") (pinfunction "1_1") (pintype "passive"))
      (node (ref "U3") (pin "4") (pinfunction "IN_4") (pintype "passive"))
      (node (ref "USB1") (pin "1") (pinfunction "+5V_1") (pintype "passive"))
    )
    (net (code "75") (name "VSYS") (class "Default")
      (node (ref "C16") (pin "1") (pinfunction "1_1") (pintype "passive"))
      (node (ref "C17") (pin "1") (pinfunction "1_1") (pintype "passive"))
      (node (ref "C18") (pin "1") (pinfunction "1_1") (pintype "passive"))
      (node (ref "C19") (pin "1") (pinfunction "1_1") (pintype "passive"))
      (node (ref "C24") (pin "2") (pinfunction "2_2") (pintype "passive"))
      (node (ref "C25") (pin "1") (pinfunction "A_1") (pintype "passive"))
      (node (ref "D1") (pin "2") (pinfunction "K_2") (pintype "passive"))
      (node (ref "D2") (pin "2") (pinfunction "K_2") (pintype "passive"))
      (node (ref "D3") (pin "2") (pinfunction "K_2") (pintype "passive"))
      (node (ref "D4") (pin "2") (pinfunction "K_2") (pintype "passive"))
      (node (ref "L5") (pin "1") (pinfunction "1_1") (pintype "passive"))
      (node (ref "M1") (pin "1") (pinfunction "1_1") (pintype "passive"))
      (node (ref "M2") (pin "2") (pinfunction "2_2") (pintype "passive"))
      (node (ref "M3") (pin "1") (pinfunction "1_1") (pintype "passive"))
      (node (ref "M4") (pin "2") (pinfunction "2_2") (pintype "passive"))
      (node (ref "R16") (pin "2") (pinfunction "2_2") (pintype "passive"))
      (node (ref "S1") (pin "1") (pinfunction "1_1") (pintype "passive"))
      (node (ref "S1") (pin "6") (pinfunction "6_6") (pintype "passive"))
      (node (ref "U5") (pin "4") (pinfunction "SD_4") (pintype "passive"))
      (node (ref "U5") (pin "5") (pinfunction "VIN_5") (pintype "passive"))
    )
    (net (code "76") (name "unconnected-(U1-NC-Pad44)") (class "Default")
      (node (ref "U1") (pin "44") (pinfunction "NC_44") (pintype "passive"))
    )
    (net (code "77") (name "unconnected-(U2-DNC-Pad13)") (class "Default")
      (node (ref "U2") (pin "13") (pinfunction "DNC_13") (pintype "passive"))
    )
    (net (code "78") (name "unconnected-(U4-BYP-Pad4)") (class "Default")
      (node (ref "U4") (pin "4") (pinfunction "BYP_4") (pintype "passive"))
    )
    (net (code "79") (name "unconnected-(U6-INT-Pad12)") (class "Default")
      (node (ref "U6") (pin "12") (pinfunction "INT_12") (pintype "passive"))
    )
    (net (code "80") (name "unconnected-(U6-NC-Pad2)") (class "Default")
      (node (ref "U6") (pin "2") (pinfunction "NC_2") (pintype "passive"))
    )
    (net (code "81") (name "unconnected-(U6-NC-Pad3)") (class "Default")
      (node (ref "U6") (pin "3") (pinfunction "NC_3") (pintype "passive"))
    )
    (net (code "82") (name "unconnected-(U6-NC-Pad4)") (class "Default")
      (node (ref "U6") (pin "4") (pinfunction "NC_4") (pintype "passive"))
    )
    (net (code "83") (name "unconnected-(U6-NC-Pad5)") (class "Default")
      (node (ref "U6") (pin "5") (pinfunction "NC_5") (pintype "passive"))
    )
    (net (code "84") (name "unconnected-(U6-NC-Pad6)") (class "Default")
      (node (ref "U6") (pin "6") (pinfunction "NC_6") (pintype "passive"))
    )
    (net (code "85") (name "unconnected-(U6-NC-Pad14)") (class "Default")
      (node (ref "U6") (pin "14") (pinfunction "NC_14") (pintype "passive"))
    )
    (net (code "86") (name "unconnected-(U6-NC-Pad15)") (class "Default")
      (node (ref "U6") (pin "15") (pinfunction "NC_15") (pintype "passive"))
    )
    (net (code "87") (name "unconnected-(U6-NC-Pad16)") (class "Default")
      (node (ref "U6") (pin "16") (pinfunction "NC_16") (pintype "passive"))
    )
    (net (code "88") (name "unconnected-(U6-NC-Pad17)") (class "Default")
      (node (ref "U6") (pin "17") (pinfunction "NC_17") (pintype "passive"))
    )
    (net (code "89") (name "unconnected-(U6-RESV-Pad19)") (class "Default")
      (node (ref "U6") (pin "19") (pinfunction "RESV_19") (pintype "passive"))
    )
    (net (code "90") (name "unconnected-(USB1-D+-Pad3)") (class "Default")
      (node (ref "USB1") (pin "3") (pinfunction "D+_3") (pintype "passive"))
    )
    (net (code "91") (name "unconnected-(USB1-D--Pad2)") (class "Default")
      (node (ref "USB1") (pin "2") (pinfunction "D-_2") (pintype "passive"))
    )
    (net (code "92") (name "unconnected-(USB1-ID-Pad4)") (class "Default")
      (node (ref "USB1") (pin "4") (pinfunction "ID_4") (pintype "passive"))
    )
    (net (code "93") (name "unconnected-(Y1-Pad2)") (class "Default")
      (node (ref "Y1") (pin "2") (pinfunction "2_2") (pintype "passive"))
    )
  )
)
